# Schematic.net
KiCad netlist of a schematic drawn in Altium Designer
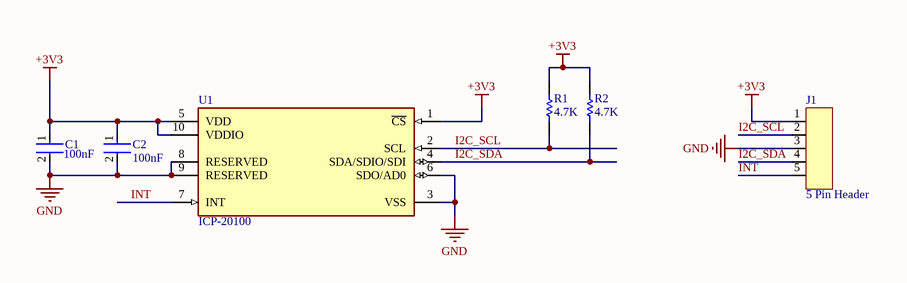
[diagram p0: Schematic.SchDoc]

(export (version "E")
  (design (tool "Eeschema 10.0.6"))
  (components
    (comp (ref "C1")
      (value "100nF")
      (footprint "FP-CC0805-0_85-MFG")
      (description "CAP CER 0.1UF 50V X7R 0805 CC0805KRX7R9BB104")
      (fields (field (name "TOLERANCE") "0.1") (field (name "MANUFACTURER PART NUMBER") "CC0805KRX7R9BB104"))
      (libsource (lib "Altium Content Vault") (part "11868f565c42a9108669ba33697ecf6"))
    )
    (comp (ref "C2")
      (value "100nF")
      (footprint "FP-CC0805-0_85-MFG")
      (description "CAP CER 0.1UF 50V X7R 0805 CC0805KRX7R9BB104")
      (fields (field (name "TOLERANCE") "0.1") (field (name "MANUFACTURER PART NUMBER") "CC0805KRX7R9BB104"))
      (libsource (lib "Altium Content Vault") (part "11868f565c42a9108669ba33697ecf6"))
    )
    (comp (ref "J1")
      (value "5 Pin Header")
      (footprint "5Pin 100mils Connector")
      (description "5 Pin Vertical Header Connector 100 mils spacing 40 mils hole")
      (libsource (lib "PersonalSchematicLib") (part "5Pin 100mils Connector"))
    )
    (comp (ref "R1")
      (value "4.7K")
      (footprint "YAGO-RC0805_M")
      (fields
        (field (name "TOLERANCE") "+/- 1%")
        (field (name "PARTNUMBER") "RC0805FR-074K7L")
        (field (name "POWER") "0.125 W")
      )
      (libsource (lib "Altium Content Vault") (part "YAGO-RES-2"))
    )
    (comp (ref "R2")
      (value "4.7K")
      (footprint "YAGO-RC0805_M")
      (fields
        (field (name "TOLERANCE") "+/- 1%")
        (field (name "PARTNUMBER") "RC0805FR-074K7L")
        (field (name "POWER") "0.125 W")
      )
      (libsource (lib "Altium Content Vault") (part "YAGO-RES-2"))
    )
    (comp (ref "U1")
      (value "ICP-20100")
      (footprint "FP-ICP-20100-MFG")
      (description "ICP-20100 Barometric Pressure and Temperature Sensor IC Digital Output 1.8V/3.3V 10-Pin LGA T/R")
      (libsource (lib "Altium Content Vault") (part "2c5c2094cf923c2d68761797ff94764"))
    )
  )
  (nets
    (net (code "1") (name "+3V3") (class "Default")
      (node (ref "C1") (pin "1") (pinfunction "1_1") (pintype "passive"))
      (node (ref "C2") (pin "1") (pinfunction "1_1") (pintype "passive"))
      (node (ref "J1") (pin "1") (pintype "passive"))
      (node (ref "R1") (pin "1") (pinfunction "1_1") (pintype "passive"))
      (node (ref "R2") (pin "1") (pinfunction "1_1") (pintype "passive"))
      (node (ref "U1") (pin "1") (pinfunction "~{CS}_1") (pintype "input"))
      (node (ref "U1") (pin "10") (pinfunction "VDDIO_10") (pintype "power_in"))
      (node (ref "U1") (pin "5") (pinfunction "VDD_5") (pintype "power_in"))
    )
    (net (code "2") (name "/I2C_SCL") (class "Default")
      (node (ref "J1") (pin "2") (pintype "passive"))
      (node (ref "R1") (pin "2") (pinfunction "2_2") (pintype "passive"))
      (node (ref "U1") (pin "2") (pinfunction "SCL_2") (pintype "input"))
    )
    (net (code "3") (name "/I2C_SDA") (class "Default")
      (node (ref "J1") (pin "4") (pintype "passive"))
      (node (ref "R2") (pin "2") (pinfunction "2_2") (pintype "passive"))
      (node (ref "U1") (pin "4") (pinfunction "SDA/SDIO/SDI_4") (pintype "bidirectional"))
    )
    (net (code "4") (name "/INT") (class "Default")
      (node (ref "J1") (pin "5") (pintype "passive"))
      (node (ref "U1") (pin "7") (pinfunction "INT_7") (pintype "input"))
    )
    (net (code "5") (name "GND") (class "Default")
      (node (ref "C1") (pin "2") (pinfunction "2_2") (pintype "passive"))
      (node (ref "C2") (pin "2") (pinfunction "2_2") (pintype "passive"))
      (node (ref "J1") (pin "3") (pintype "passive"))
      (node (ref "U1") (pin "3") (pinfunction "VSS_3") (pintype "power_in"))
      (node (ref "U1") (pin "6") (pinfunction "SDO/AD0_6") (pintype "bidirectional"))
      (node (ref "U1") (pin "8") (pinfunction "RESERVED_8") (pintype "passive"))
      (node (ref "U1") (pin "9") (pinfunction "RESERVED_9") (pintype "passive"))
    )
  )
)
